# EEG_TI.net
KiCad netlist of a schematic drawn in Altium Designer
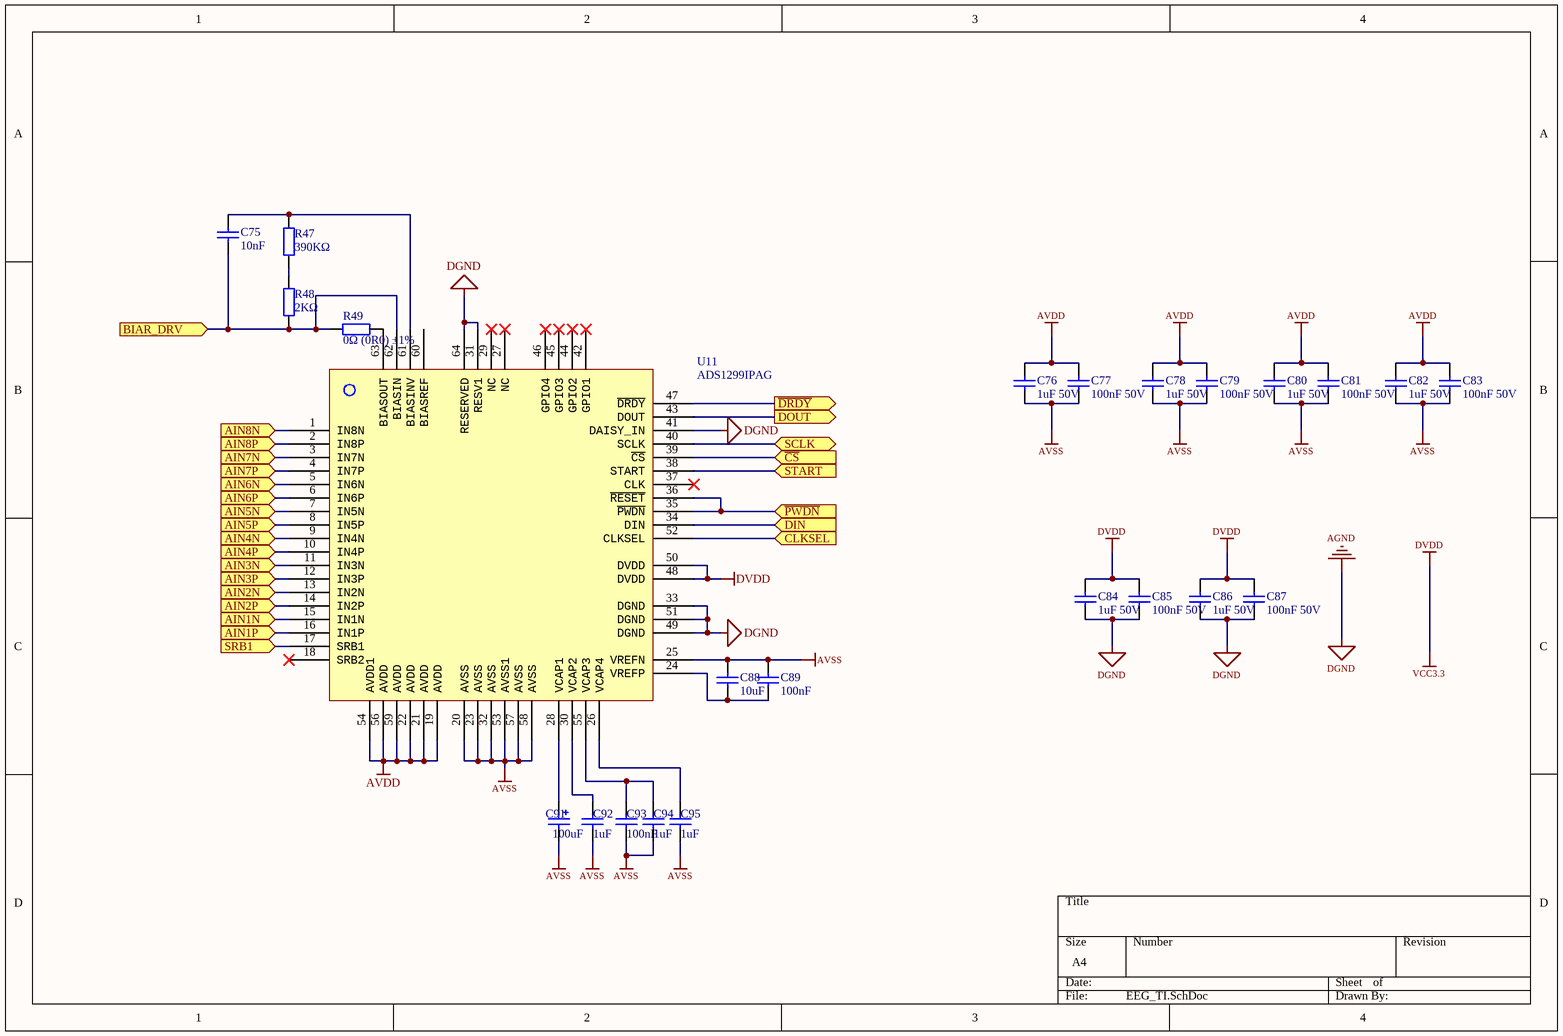
[diagram p0: EEG_TI.SchDoc]

(export (version "E")
  (design (tool "Eeschema 10.0.6"))
  (components
    (comp (ref "C75")
      (value "10nF")
      (footprint "0402_C")
      (description "贴片电容")
      (libsource (lib "Miscellaneous Devices LC") (part "0402 10nF (103) 10% 50V"))
    )
    (comp (ref "C76")
      (value "1uF 50V")
      (footprint "0402_C")
      (description "贴片电容")
      (libsource (lib "Miscellaneous Devices LC") (part "0603 10nF (103) 10% 50V"))
    )
    (comp (ref "C77")
      (value "100nF 50V")
      (footprint "0402_C")
      (description "贴片电容")
      (libsource (lib "Miscellaneous Devices LC") (part "0603 10nF (103) 10% 50V"))
    )
    (comp (ref "C78")
      (value "1uF 50V")
      (footprint "0402_C")
      (description "贴片电容")
      (libsource (lib "Miscellaneous Devices LC") (part "0603 10nF (103) 10% 50V"))
    )
    (comp (ref "C79")
      (value "100nF 50V")
      (footprint "0402_C")
      (description "贴片电容")
      (libsource (lib "Miscellaneous Devices LC") (part "0603 10nF (103) 10% 50V"))
    )
    (comp (ref "C80")
      (value "1uF 50V")
      (footprint "0402_C")
      (description "贴片电容")
      (libsource (lib "Miscellaneous Devices LC") (part "0603 10nF (103) 10% 50V"))
    )
    (comp (ref "C81")
      (value "100nF 50V")
      (footprint "0402_C")
      (description "贴片电容")
      (libsource (lib "Miscellaneous Devices LC") (part "0603 10nF (103) 10% 50V"))
    )
    (comp (ref "C82")
      (value "1uF 50V")
      (footprint "0402_C")
      (description "贴片电容")
      (libsource (lib "Miscellaneous Devices LC") (part "0603 10nF (103) 10% 50V"))
    )
    (comp (ref "C83")
      (value "100nF 50V")
      (footprint "0402_C")
      (description "贴片电容")
      (libsource (lib "Miscellaneous Devices LC") (part "0603 10nF (103) 10% 50V"))
    )
    (comp (ref "C84")
      (value "1uF 50V")
      (footprint "0402_C")
      (description "贴片电容")
      (libsource (lib "Miscellaneous Devices LC") (part "0603 10nF (103) 10% 50V"))
    )
    (comp (ref "C85")
      (value "100nF 50V")
      (footprint "0402_C")
      (description "贴片电容")
      (libsource (lib "Miscellaneous Devices LC") (part "0603 10nF (103) 10% 50V"))
    )
    (comp (ref "C86")
      (value "1uF 50V")
      (footprint "0402_C")
      (description "贴片电容")
      (libsource (lib "Miscellaneous Devices LC") (part "0603 10nF (103) 10% 50V"))
    )
    (comp (ref "C87")
      (value "100nF 50V")
      (footprint "0402_C")
      (description "贴片电容")
      (libsource (lib "Miscellaneous Devices LC") (part "0603 10nF (103) 10% 50V"))
    )
    (comp (ref "C88")
      (value "10uF")
      (footprint "0402_C")
      (description "贴片电容")
      (libsource (lib "Miscellaneous Devices LC") (part "0402 10uF (106) 20% 6.3V"))
    )
    (comp (ref "C89")
      (value "100nF")
      (footprint "0402_C")
      (description "贴片电容")
      (libsource (lib "Miscellaneous Devices LC") (part "0402 100nF (104) 10% 16V"))
    )
    (comp (ref "C91")
      (value "100uF")
      (footprint "CASE-B_3528")
      (description "钽电容")
      (libsource (lib "Miscellaneous Devices LC") (part "3528 100uF (107) 10% 6.3V"))
    )
    (comp (ref "C92")
      (value "1uF")
      (footprint "0603_C")
      (description "贴片电容")
      (libsource (lib "Miscellaneous Devices LC") (part "0603 1uF (105) 10% 50V"))
    )
    (comp (ref "C93")
      (value "100nF")
      (footprint "0402_C")
      (description "贴片电容")
      (libsource (lib "Miscellaneous Devices LC") (part "0402 100nF (104) 10% 16V"))
    )
    (comp (ref "C94")
      (value "1uF")
      (footprint "0603_C")
      (description "贴片电容")
      (libsource (lib "Miscellaneous Devices LC") (part "0603 1uF (105) 10% 50V"))
    )
    (comp (ref "C95")
      (value "1uF")
      (footprint "0603_C")
      (description "贴片电容")
      (libsource (lib "Miscellaneous Devices LC") (part "0603 1uF (105) 10% 50V"))
    )
    (comp (ref "R47")
      (value "390KΩ")
      (footprint "0603_R")
      (description "贴片电阻")
      (libsource (lib "Miscellaneous Devices LC") (part "0603 390KΩ (3903) 1%"))
    )
    (comp (ref "R48")
      (value "2KΩ")
      (footprint "0402_R")
      (description "贴片电阻")
      (libsource (lib "Miscellaneous Devices LC") (part "0402 2KΩ (2001) 1%"))
    )
    (comp (ref "R49")
      (value "0Ω (0R0) ±1%")
      (footprint "0402_R")
      (description "贴片电阻")
      (libsource (lib "Miscellaneous Devices LC") (part "0402 0Ω (0R0) 1%"))
    )
    (comp (ref "U11")
      (value "ADS1299IPAG")
      (footprint "ADS1299")
      (libsource (lib "EEG") (part "ADS1299IPAG"))
    )
  )
  (nets
    (net (code "1") (name "/AIN1N") (class "Default")
      (node (ref "U11") (pin "15") (pinfunction "IN1N_15") (pintype "passive"))
    )
    (net (code "2") (name "/AIN1P") (class "Default")
      (node (ref "U11") (pin "16") (pinfunction "IN1P_16") (pintype "passive"))
    )
    (net (code "3") (name "/AIN2N") (class "Default")
      (node (ref "U11") (pin "13") (pinfunction "IN2N_13") (pintype "passive"))
    )
    (net (code "4") (name "/AIN2P") (class "Default")
      (node (ref "U11") (pin "14") (pinfunction "IN2P_14") (pintype "passive"))
    )
    (net (code "5") (name "/AIN3N") (class "Default")
      (node (ref "U11") (pin "11") (pinfunction "IN3N_11") (pintype "passive"))
    )
    (net (code "6") (name "/AIN3P") (class "Default")
      (node (ref "U11") (pin "12") (pinfunction "IN3P_12") (pintype "passive"))
    )
    (net (code "7") (name "/AIN4N") (class "Default")
      (node (ref "U11") (pin "9") (pinfunction "IN4N_9") (pintype "passive"))
    )
    (net (code "8") (name "/AIN4P") (class "Default")
      (node (ref "U11") (pin "10") (pinfunction "IN4P_10") (pintype "passive"))
    )
    (net (code "9") (name "/AIN5N") (class "Default")
      (node (ref "U11") (pin "7") (pinfunction "IN5N_7") (pintype "passive"))
    )
    (net (code "10") (name "/AIN5P") (class "Default")
      (node (ref "U11") (pin "8") (pinfunction "IN5P_8") (pintype "passive"))
    )
    (net (code "11") (name "/AIN6N") (class "Default")
      (node (ref "U11") (pin "5") (pinfunction "IN6N_5") (pintype "passive"))
    )
    (net (code "12") (name "/AIN6P") (class "Default")
      (node (ref "U11") (pin "6") (pinfunction "IN6P_6") (pintype "passive"))
    )
    (net (code "13") (name "/AIN7N") (class "Default")
      (node (ref "U11") (pin "3") (pinfunction "IN7N_3") (pintype "passive"))
    )
    (net (code "14") (name "/AIN7P") (class "Default")
      (node (ref "U11") (pin "4") (pinfunction "IN7P_4") (pintype "passive"))
    )
    (net (code "15") (name "/AIN8N") (class "Default")
      (node (ref "U11") (pin "1") (pinfunction "IN8N_1") (pintype "passive"))
    )
    (net (code "16") (name "/AIN8P") (class "Default")
      (node (ref "U11") (pin "2") (pinfunction "IN8P_2") (pintype "passive"))
    )
    (net (code "17") (name "/BIAR_DRV") (class "Default")
      (node (ref "C75") (pin "1") (pinfunction "1_1") (pintype "passive"))
      (node (ref "R48") (pin "1") (pinfunction "1_1") (pintype "passive"))
      (node (ref "R49") (pin "2") (pinfunction "2_2") (pintype "passive"))
      (node (ref "U11") (pin "62") (pinfunction "BIASIN_62") (pintype "passive"))
    )
    (net (code "18") (name "/CLKSEL") (class "Default")
      (node (ref "U11") (pin "52") (pinfunction "CLKSEL_52") (pintype "passive"))
    )
    (net (code "19") (name "/DIN") (class "Default")
      (node (ref "U11") (pin "34") (pinfunction "DIN_34") (pintype "passive"))
    )
    (net (code "20") (name "/DOUT") (class "Default")
      (node (ref "U11") (pin "43") (pinfunction "DOUT_43") (pintype "passive"))
    )
    (net (code "21") (name "/SCLK") (class "Default")
      (node (ref "U11") (pin "40") (pinfunction "SCLK_40") (pintype "passive"))
    )
    (net (code "22") (name "/SRB1") (class "Default")
      (node (ref "U11") (pin "17") (pinfunction "SRB1_17") (pintype "passive"))
    )
    (net (code "23") (name "/START") (class "Default")
      (node (ref "U11") (pin "38") (pinfunction "START_38") (pintype "passive"))
    )
    (net (code "24") (name "/~{CS}") (class "Default")
      (node (ref "U11") (pin "39") (pinfunction "~{CS}_39") (pintype "passive"))
    )
    (net (code "25") (name "/~{DRDY}") (class "Default")
      (node (ref "U11") (pin "47") (pinfunction "~{DRDY}_47") (pintype "passive"))
    )
    (net (code "26") (name "/~{PWDN}") (class "Default")
      (node (ref "U11") (pin "35") (pinfunction "~{PWDN}_35") (pintype "passive"))
      (node (ref "U11") (pin "36") (pinfunction "~{RESET}_36") (pintype "passive"))
    )
    (net (code "27") (name "AGND") (class "Default")
      (node (ref "C84") (pin "2") (pinfunction "2_2") (pintype "passive"))
      (node (ref "C85") (pin "2") (pinfunction "2_2") (pintype "passive"))
      (node (ref "C86") (pin "2") (pinfunction "2_2") (pintype "passive"))
      (node (ref "C87") (pin "2") (pinfunction "2_2") (pintype "passive"))
      (node (ref "U11") (pin "31") (pinfunction "RESV1_31") (pintype "passive"))
      (node (ref "U11") (pin "33") (pinfunction "DGND_33") (pintype "passive"))
      (node (ref "U11") (pin "41") (pinfunction "DAISY_IN_41") (pintype "passive"))
      (node (ref "U11") (pin "49") (pinfunction "DGND_49") (pintype "passive"))
      (node (ref "U11") (pin "51") (pinfunction "DGND_51") (pintype "passive"))
      (node (ref "U11") (pin "64") (pinfunction "RESERVED_64") (pintype "passive"))
    )
    (net (code "28") (name "AVDD") (class "Default")
      (node (ref "C76") (pin "1") (pinfunction "1_1") (pintype "passive"))
      (node (ref "C77") (pin "1") (pinfunction "1_1") (pintype "passive"))
      (node (ref "C78") (pin "1") (pinfunction "1_1") (pintype "passive"))
      (node (ref "C79") (pin "1") (pinfunction "1_1") (pintype "passive"))
      (node (ref "C80") (pin "1") (pinfunction "1_1") (pintype "passive"))
      (node (ref "C81") (pin "1") (pinfunction "1_1") (pintype "passive"))
      (node (ref "C82") (pin "1") (pinfunction "1_1") (pintype "passive"))
      (node (ref "C83") (pin "1") (pinfunction "1_1") (pintype "passive"))
      (node (ref "U11") (pin "19") (pinfunction "AVDD_19") (pintype "passive"))
      (node (ref "U11") (pin "21") (pinfunction "AVDD_21") (pintype "passive"))
      (node (ref "U11") (pin "22") (pinfunction "AVDD_22") (pintype "passive"))
      (node (ref "U11") (pin "54") (pinfunction "AVDD1_54") (pintype "passive"))
      (node (ref "U11") (pin "56") (pinfunction "AVDD_56") (pintype "passive"))
      (node (ref "U11") (pin "59") (pinfunction "AVDD_59") (pintype "passive"))
    )
    (net (code "29") (name "AVSS") (class "Default")
      (node (ref "C76") (pin "2") (pinfunction "2_2") (pintype "passive"))
      (node (ref "C77") (pin "2") (pinfunction "2_2") (pintype "passive"))
      (node (ref "C78") (pin "2") (pinfunction "2_2") (pintype "passive"))
      (node (ref "C79") (pin "2") (pinfunction "2_2") (pintype "passive"))
      (node (ref "C80") (pin "2") (pinfunction "2_2") (pintype "passive"))
      (node (ref "C81") (pin "2") (pinfunction "2_2") (pintype "passive"))
      (node (ref "C82") (pin "2") (pinfunction "2_2") (pintype "passive"))
      (node (ref "C83") (pin "2") (pinfunction "2_2") (pintype "passive"))
      (node (ref "C88") (pin "1") (pinfunction "1_1") (pintype "passive"))
      (node (ref "C89") (pin "2") (pinfunction "2_2") (pintype "passive"))
      (node (ref "C91") (pin "2") (pinfunction "2_2") (pintype "passive"))
      (node (ref "C92") (pin "1") (pinfunction "1_1") (pintype "passive"))
      (node (ref "C93") (pin "1") (pinfunction "1_1") (pintype "passive"))
      (node (ref "C94") (pin "1") (pinfunction "1_1") (pintype "passive"))
      (node (ref "C95") (pin "1") (pinfunction "1_1") (pintype "passive"))
      (node (ref "U11") (pin "20") (pinfunction "AVSS_20") (pintype "passive"))
      (node (ref "U11") (pin "23") (pinfunction "AVSS_23") (pintype "passive"))
      (node (ref "U11") (pin "25") (pinfunction "VREFN_25") (pintype "passive"))
      (node (ref "U11") (pin "32") (pinfunction "AVSS_32") (pintype "passive"))
      (node (ref "U11") (pin "53") (pinfunction "AVSS1_53") (pintype "passive"))
      (node (ref "U11") (pin "57") (pinfunction "AVSS_57") (pintype "passive"))
      (node (ref "U11") (pin "58") (pinfunction "AVSS_58") (pintype "passive"))
    )
    (net (code "30") (name "DVDD") (class "Default")
      (node (ref "C84") (pin "1") (pinfunction "1_1") (pintype "passive"))
      (node (ref "C85") (pin "1") (pinfunction "1_1") (pintype "passive"))
      (node (ref "C86") (pin "1") (pinfunction "1_1") (pintype "passive"))
      (node (ref "C87") (pin "1") (pinfunction "1_1") (pintype "passive"))
      (node (ref "U11") (pin "48") (pinfunction "DVDD_48") (pintype "passive"))
      (node (ref "U11") (pin "50") (pinfunction "DVDD_50") (pintype "passive"))
    )
    (net (code "31") (name "Net-(R47-Pad1)") (class "Default")
      (node (ref "R47") (pin "1") (pinfunction "1_1") (pintype "passive"))
      (node (ref "R48") (pin "2") (pinfunction "2_2") (pintype "passive"))
    )
    (net (code "32") (name "Net-(U11-BIASINV)") (class "Default")
      (node (ref "C75") (pin "2") (pinfunction "2_2") (pintype "passive"))
      (node (ref "R47") (pin "2") (pinfunction "2_2") (pintype "passive"))
      (node (ref "U11") (pin "61") (pinfunction "BIASINV_61") (pintype "passive"))
    )
    (net (code "33") (name "Net-(U11-BIASOUT)") (class "Default")
      (node (ref "R49") (pin "1") (pinfunction "1_1") (pintype "passive"))
      (node (ref "U11") (pin "63") (pinfunction "BIASOUT_63") (pintype "passive"))
    )
    (net (code "34") (name "Net-(U11-VCAP1)") (class "Default")
      (node (ref "C91") (pin "1") (pinfunction "1_1") (pintype "passive"))
      (node (ref "U11") (pin "28") (pinfunction "VCAP1_28") (pintype "passive"))
    )
    (net (code "35") (name "Net-(U11-VCAP2)") (class "Default")
      (node (ref "C92") (pin "2") (pinfunction "2_2") (pintype "passive"))
      (node (ref "U11") (pin "30") (pinfunction "VCAP2_30") (pintype "passive"))
    )
    (net (code "36") (name "Net-(U11-VCAP3)") (class "Default")
      (node (ref "C93") (pin "2") (pinfunction "2_2") (pintype "passive"))
      (node (ref "C94") (pin "2") (pinfunction "2_2") (pintype "passive"))
      (node (ref "U11") (pin "55") (pinfunction "VCAP3_55") (pintype "passive"))
    )
    (net (code "37") (name "Net-(U11-VCAP4)") (class "Default")
      (node (ref "C95") (pin "2") (pinfunction "2_2") (pintype "passive"))
      (node (ref "U11") (pin "26") (pinfunction "VCAP4_26") (pintype "passive"))
    )
    (net (code "38") (name "Net-(U11-VREFP)") (class "Default")
      (node (ref "C88") (pin "2") (pinfunction "2_2") (pintype "passive"))
      (node (ref "C89") (pin "1") (pinfunction "1_1") (pintype "passive"))
      (node (ref "U11") (pin "24") (pinfunction "VREFP_24") (pintype "passive"))
    )
    (net (code "39") (name "unconnected-(U11-BIASREF-Pad60)") (class "Default")
      (node (ref "U11") (pin "60") (pinfunction "BIASREF_60") (pintype "passive"))
    )
    (net (code "40") (name "unconnected-(U11-CLK-Pad37)") (class "Default")
      (node (ref "U11") (pin "37") (pinfunction "CLK_37") (pintype "passive+no_connect"))
    )
    (net (code "41") (name "unconnected-(U11-GPIO1-Pad42)") (class "Default")
      (node (ref "U11") (pin "42") (pinfunction "GPIO1_42") (pintype "passive+no_connect"))
    )
    (net (code "42") (name "unconnected-(U11-GPIO2-Pad44)") (class "Default")
      (node (ref "U11") (pin "44") (pinfunction "GPIO2_44") (pintype "passive+no_connect"))
    )
    (net (code "43") (name "unconnected-(U11-GPIO3-Pad45)") (class "Default")
      (node (ref "U11") (pin "45") (pinfunction "GPIO3_45") (pintype "passive+no_connect"))
    )
    (net (code "44") (name "unconnected-(U11-GPIO4-Pad46)") (class "Default")
      (node (ref "U11") (pin "46") (pinfunction "GPIO4_46") (pintype "passive+no_connect"))
    )
    (net (code "45") (name "unconnected-(U11-NC-Pad27)") (class "Default")
      (node (ref "U11") (pin "27") (pinfunction "NC_27") (pintype "passive+no_connect"))
    )
    (net (code "46") (name "unconnected-(U11-NC-Pad29)") (class "Default")
      (node (ref "U11") (pin "29") (pinfunction "NC_29") (pintype "passive+no_connect"))
    )
    (net (code "47") (name "unconnected-(U11-SRB2-Pad18)") (class "Default")
      (node (ref "U11") (pin "18") (pinfunction "SRB2_18") (pintype "passive+no_connect"))
    )
  )
)
